# Page07_CPU_PHY.net
KiCad netlist of a schematic drawn in Altium Designer
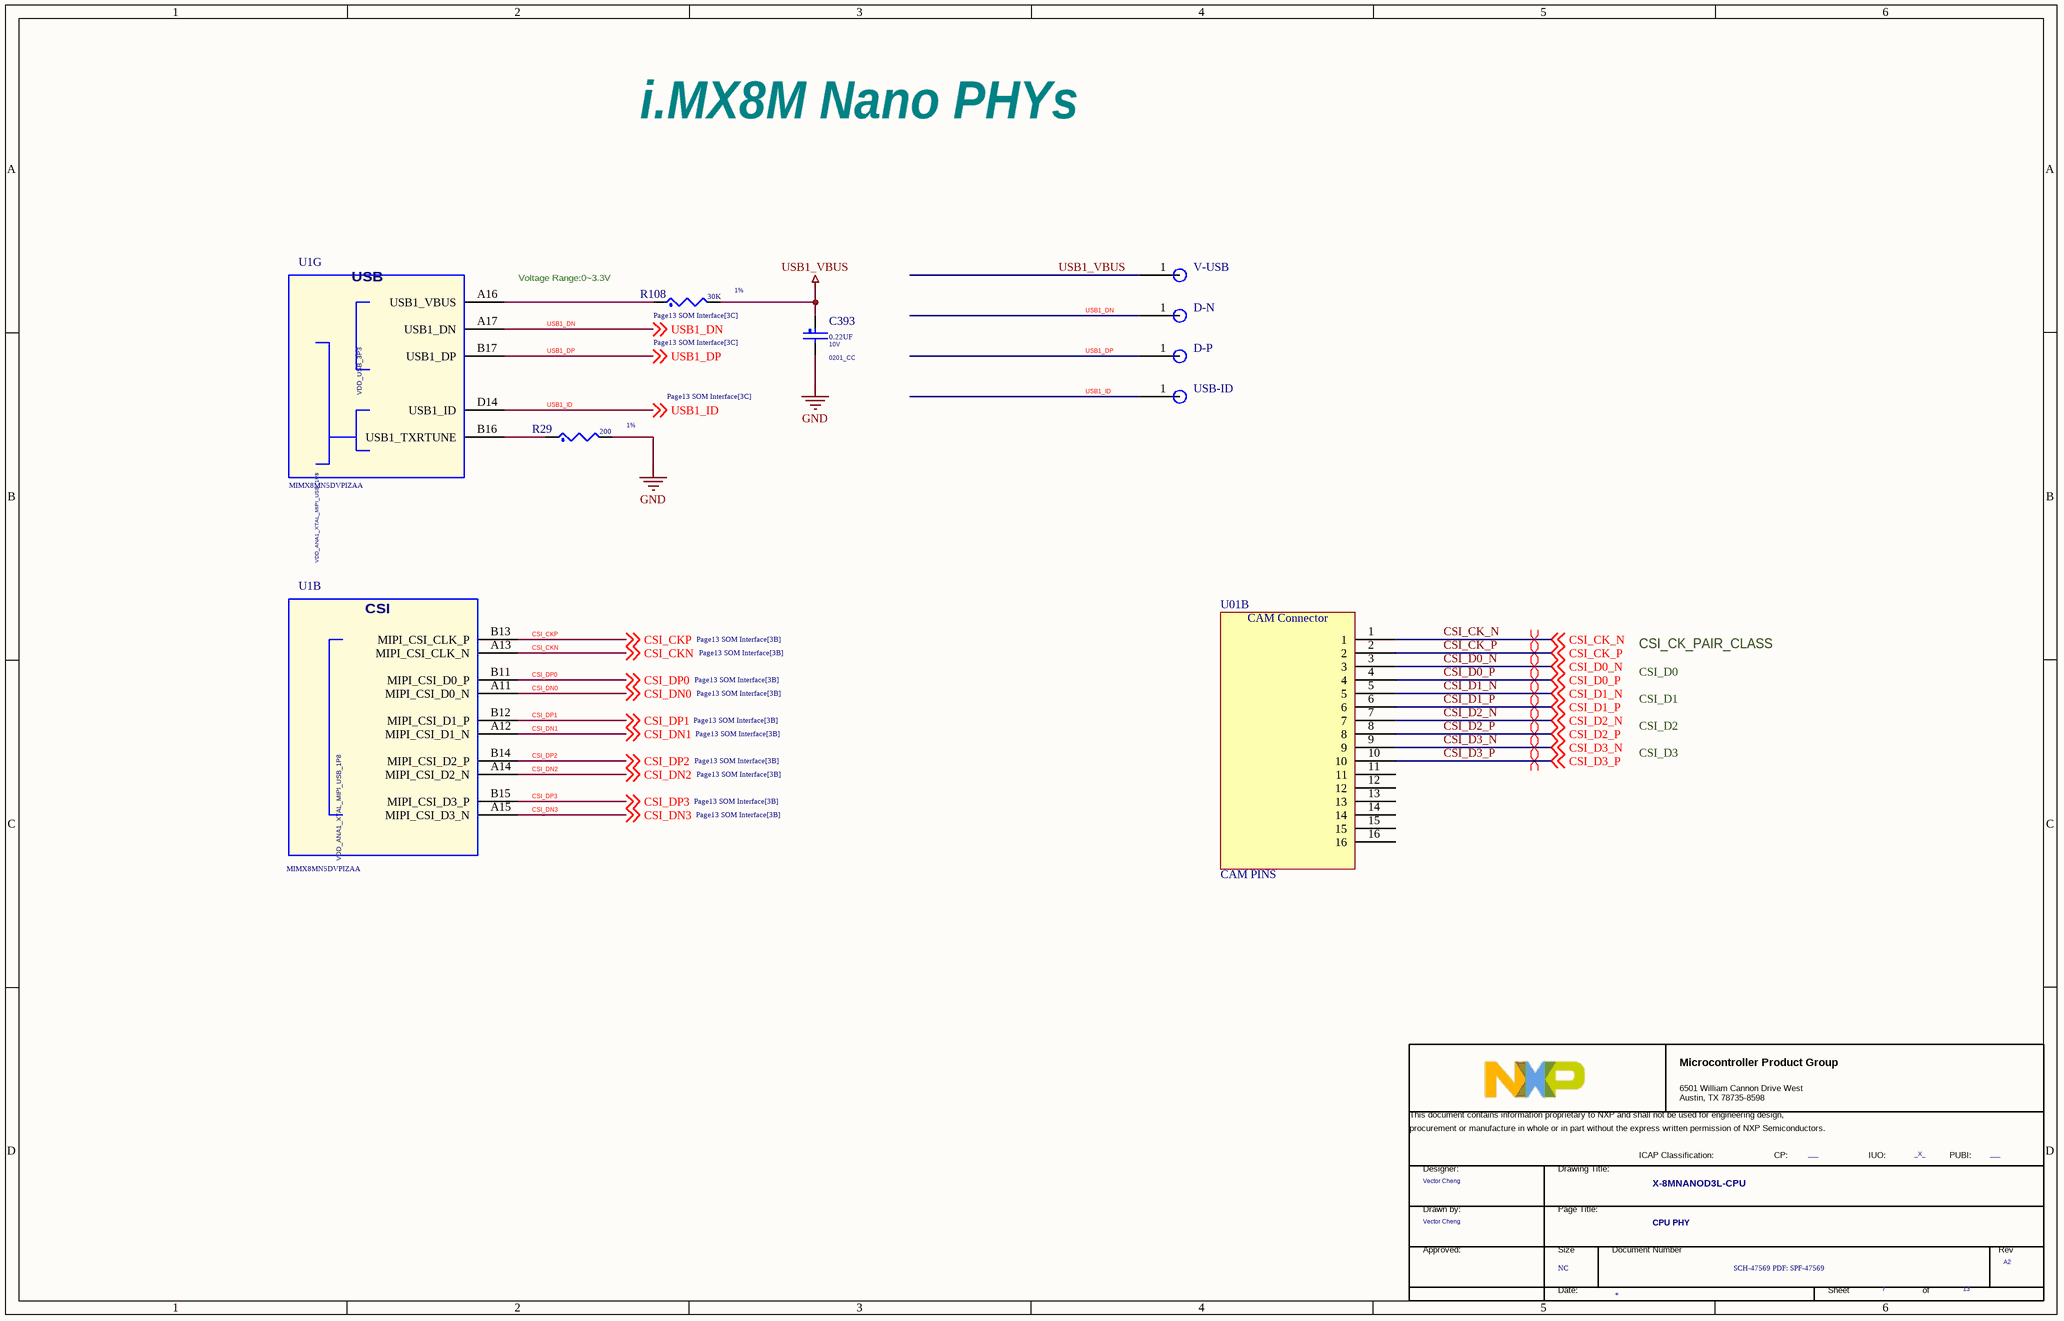
[diagram p0: Page07 CPU PHY.SchDoc]

(export (version "E")
  (design (tool "Eeschema 10.0.6"))
  (components
    (comp (ref "C393")
      (value "0.22UF")
      (footprint "0201_CC - C")
      (description "CAP CER 0.22UF 10V 20% X5R 0201")
      (fields
        (field (name "VOLTAGE") "10V")
        (field (name "TOLERANCE") "20%")
        (field (name "PCB FOOTPRINT") "0201_CC")
      )
      (libsource (lib "*") (part "CAP_NP"))
    )
    (comp (ref "D-N")
      (value "Test Pin1")
      (footprint "Test Pin")
      (libsource (lib "Altium starter project NANO") (part "Test Pin1"))
    )
    (comp (ref "D-P")
      (value "Test Pin1")
      (footprint "Test Pin")
      (libsource (lib "Altium starter project NANO") (part "Test Pin1"))
    )
    (comp (ref "R29")
      (value "200")
      (footprint "0201_RES")
      (description "RES MF 200 OHM 1/20W 1% 0201")
      (fields (field (name "TOLERANCE") "1%") (field (name "VOLTAGE") "25V"))
      (libsource (lib "*") (part "RES"))
    )
    (comp (ref "R108")
      (value "30K")
      (footprint "0201_RES")
      (description "RES MF 30K 1/20W 1% 0201")
      (fields (field (name "VOLTAGE") "25V") (field (name "TOLERANCE") "1%"))
      (libsource (lib "*") (part "RES"))
    )
    (comp (ref "U1")
      (value "MIMX8MN5DVPIZAA")
      (footprint "BGA306C50P21X21_1100X1100X101")
      (description "IC CPU QUAD CORTEX A53+M7 1.4GHZ -- BGA306")
      (libsource (lib "*") (part "MIMX8MN"))
    )
    (comp (ref "U01B")
      (value "CAM PINS")
      (footprint "CAM Footprint")
      (libsource (lib "Altium starter project NANO") (part "CAM PINS"))
    )
    (comp (ref "USB-ID")
      (value "Test Pin1")
      (footprint "Test Pin")
      (libsource (lib "Altium starter project NANO") (part "Test Pin1"))
    )
    (comp (ref "V-USB")
      (value "Test Pin1")
      (footprint "Test Pin")
      (libsource (lib "Altium starter project NANO") (part "Test Pin1"))
    )
  )
  (nets
    (net (code "1") (name "CSI_CKN") (class "Default")
      (node (ref "U1") (pin "A13") (pinfunction "MIPI_CSI_CLK_N_A13") (pintype "passive"))
    )
    (net (code "2") (name "CSI_CKP") (class "Default")
      (node (ref "U1") (pin "B13") (pinfunction "MIPI_CSI_CLK_P_B13") (pintype "passive"))
    )
    (net (code "3") (name "CSI_CK_N") (class "Default")
      (node (ref "U01B") (pin "1") (pinfunction "1_1") (pintype "passive"))
    )
    (net (code "4") (name "CSI_CK_P") (class "Default")
      (node (ref "U01B") (pin "2") (pinfunction "2_2") (pintype "passive"))
    )
    (net (code "5") (name "CSI_D0_N") (class "Default")
      (node (ref "U01B") (pin "3") (pinfunction "3_3") (pintype "passive"))
    )
    (net (code "6") (name "CSI_D0_P") (class "Default")
      (node (ref "U01B") (pin "4") (pinfunction "4_4") (pintype "passive"))
    )
    (net (code "7") (name "CSI_D1_N") (class "Default")
      (node (ref "U01B") (pin "5") (pinfunction "5_5") (pintype "passive"))
    )
    (net (code "8") (name "CSI_D1_P") (class "Default")
      (node (ref "U01B") (pin "6") (pinfunction "6_6") (pintype "passive"))
    )
    (net (code "9") (name "CSI_D2_N") (class "Default")
      (node (ref "U01B") (pin "7") (pinfunction "7_7") (pintype "passive"))
    )
    (net (code "10") (name "CSI_D2_P") (class "Default")
      (node (ref "U01B") (pin "8") (pinfunction "8_8") (pintype "passive"))
    )
    (net (code "11") (name "CSI_D3_N") (class "Default")
      (node (ref "U01B") (pin "9") (pinfunction "9_9") (pintype "passive"))
    )
    (net (code "12") (name "CSI_D3_P") (class "Default")
      (node (ref "U01B") (pin "10") (pinfunction "10_10") (pintype "passive"))
    )
    (net (code "13") (name "CSI_DN0") (class "Default")
      (node (ref "U1") (pin "A11") (pinfunction "MIPI_CSI_D0_N_A11") (pintype "passive"))
    )
    (net (code "14") (name "CSI_DN1") (class "Default")
      (node (ref "U1") (pin "A12") (pinfunction "MIPI_CSI_D1_N_A12") (pintype "passive"))
    )
    (net (code "15") (name "CSI_DN2") (class "Default")
      (node (ref "U1") (pin "A14") (pinfunction "MIPI_CSI_D2_N_A14") (pintype "passive"))
    )
    (net (code "16") (name "CSI_DN3") (class "Default")
      (node (ref "U1") (pin "A15") (pinfunction "MIPI_CSI_D3_N_A15") (pintype "passive"))
    )
    (net (code "17") (name "CSI_DP0") (class "Default")
      (node (ref "U1") (pin "B11") (pinfunction "MIPI_CSI_D0_P_B11") (pintype "passive"))
    )
    (net (code "18") (name "CSI_DP1") (class "Default")
      (node (ref "U1") (pin "B12") (pinfunction "MIPI_CSI_D1_P_B12") (pintype "passive"))
    )
    (net (code "19") (name "CSI_DP2") (class "Default")
      (node (ref "U1") (pin "B14") (pinfunction "MIPI_CSI_D2_P_B14") (pintype "passive"))
    )
    (net (code "20") (name "CSI_DP3") (class "Default")
      (node (ref "U1") (pin "B15") (pinfunction "MIPI_CSI_D3_P_B15") (pintype "passive"))
    )
    (net (code "21") (name "GND") (class "Default")
      (node (ref "C393") (pin "2") (pinfunction "2_2") (pintype "passive"))
      (node (ref "R29") (pin "2") (pinfunction "2_2") (pintype "passive"))
    )
    (net (code "22") (name "Net-(U1G-USB1_TXRTUNE)") (class "Default")
      (node (ref "R29") (pin "1") (pinfunction "1_1") (pintype "passive"))
      (node (ref "U1") (pin "B16") (pinfunction "USB1_TXRTUNE_B16") (pintype "passive"))
    )
    (net (code "23") (name "Net-(U1G-USB1_VBUS)") (class "Default")
      (node (ref "R108") (pin "1") (pinfunction "1_1") (pintype "passive"))
      (node (ref "U1") (pin "A16") (pinfunction "USB1_VBUS_A16") (pintype "passive"))
    )
    (net (code "24") (name "USB1_DN") (class "Default")
      (node (ref "D-N") (pin "1") (pinfunction "1_1") (pintype "passive"))
      (node (ref "U1") (pin "A17") (pinfunction "USB1_DN_A17") (pintype "passive"))
    )
    (net (code "25") (name "USB1_DP") (class "Default")
      (node (ref "D-P") (pin "1") (pinfunction "1_1") (pintype "passive"))
      (node (ref "U1") (pin "B17") (pinfunction "USB1_DP_B17") (pintype "passive"))
    )
    (net (code "26") (name "USB1_ID") (class "Default")
      (node (ref "U1") (pin "D14") (pinfunction "USB1_ID_D14") (pintype "passive"))
      (node (ref "USB-ID") (pin "1") (pinfunction "1_1") (pintype "passive"))
    )
    (net (code "27") (name "USB1_VBUS") (class "Default")
      (node (ref "C393") (pin "1") (pinfunction "1_1") (pintype "passive"))
      (node (ref "R108") (pin "2") (pinfunction "2_2") (pintype "passive"))
      (node (ref "V-USB") (pin "1") (pinfunction "1_1") (pintype "passive"))
    )
    (net (code "28") (name "unconnected-(U01B-Pad11)") (class "Default")
      (node (ref "U01B") (pin "11") (pinfunction "11_11") (pintype "passive"))
    )
    (net (code "29") (name "unconnected-(U01B-Pad12)") (class "Default")
      (node (ref "U01B") (pin "12") (pinfunction "12_12") (pintype "passive"))
    )
    (net (code "30") (name "unconnected-(U01B-Pad13)") (class "Default")
      (node (ref "U01B") (pin "13") (pinfunction "13_13") (pintype "passive"))
    )
    (net (code "31") (name "unconnected-(U01B-Pad14)") (class "Default")
      (node (ref "U01B") (pin "14") (pinfunction "14_14") (pintype "passive"))
    )
    (net (code "32") (name "unconnected-(U01B-Pad15)") (class "Default")
      (node (ref "U01B") (pin "15") (pinfunction "15_15") (pintype "passive"))
    )
    (net (code "33") (name "unconnected-(U01B-Pad16)") (class "Default")
      (node (ref "U01B") (pin "16") (pinfunction "16_16") (pintype "passive"))
    )
  )
)
